# mkwatch_btm.net
KiCad netlist of a schematic drawn in EAGLE
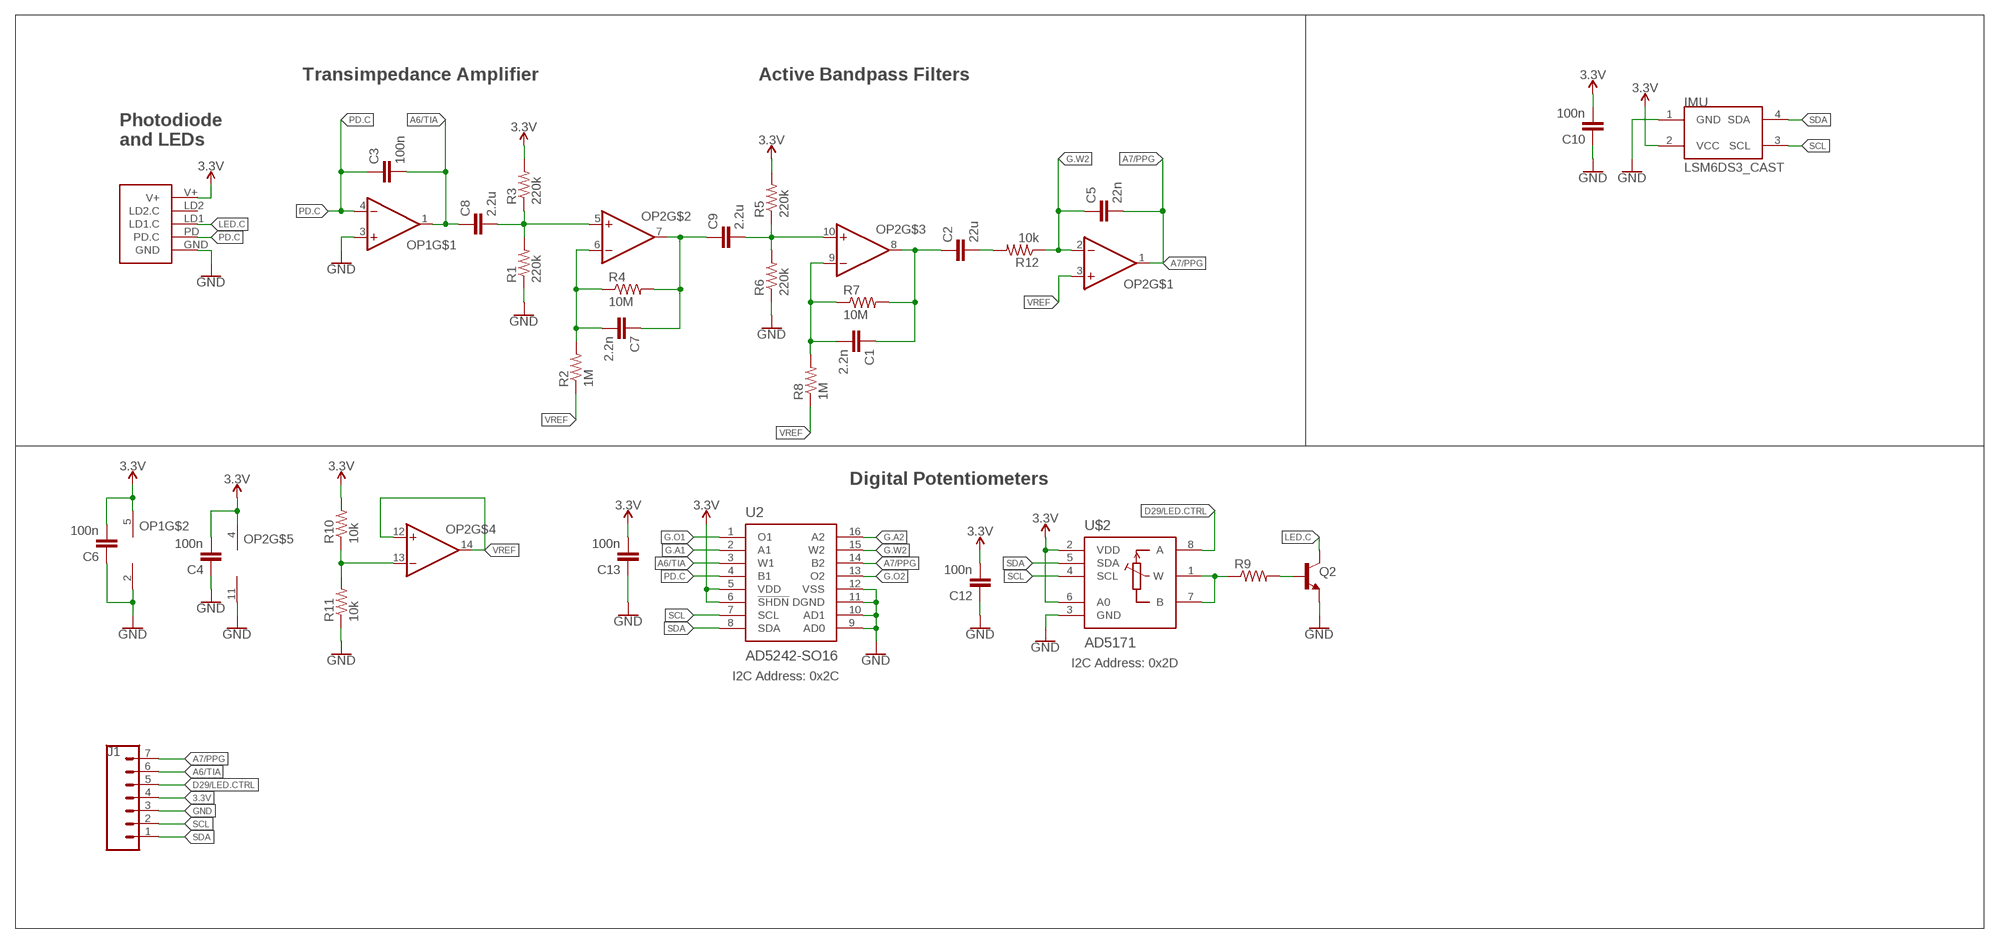
[diagram p0: schematic, sheet 1]

(export (version "E")
  (design (tool "Eeschema 10.0.6"))
  (components
    (comp (ref "C1")
      (value "2.2n")
      (footprint "eagle-import:C0603")
      (libsource (lib "eagle-import") (part "CAPACITOR0603"))
    )
    (comp (ref "C2")
      (value "22u")
      (footprint "eagle-import:C0603")
      (libsource (lib "eagle-import") (part "CAPACITOR0603"))
    )
    (comp (ref "C3")
      (value "100n")
      (footprint "eagle-import:C0603")
      (libsource (lib "eagle-import") (part "CAPACITOR0603"))
    )
    (comp (ref "C4")
      (value "100n")
      (footprint "eagle-import:C0603")
      (libsource (lib "eagle-import") (part "CAPACITOR0603"))
    )
    (comp (ref "C5")
      (value "22n")
      (footprint "eagle-import:C0603")
      (libsource (lib "eagle-import") (part "CAPACITOR0603"))
    )
    (comp (ref "C6")
      (value "100n")
      (footprint "eagle-import:C0603")
      (libsource (lib "eagle-import") (part "CAPACITOR0603"))
    )
    (comp (ref "C7")
      (value "2.2n")
      (footprint "eagle-import:C0603")
      (libsource (lib "eagle-import") (part "CAPACITOR0603"))
    )
    (comp (ref "C8")
      (value "2.2u")
      (footprint "eagle-import:C0603")
      (libsource (lib "eagle-import") (part "CAPACITOR0603"))
    )
    (comp (ref "C9")
      (value "2.2u")
      (footprint "eagle-import:C0603")
      (libsource (lib "eagle-import") (part "CAPACITOR0603"))
    )
    (comp (ref "C10")
      (value "100n")
      (footprint "eagle-import:C0603")
      (libsource (lib "eagle-import") (part "CAPACITOR0603"))
    )
    (comp (ref "C12")
      (value "100n")
      (footprint "eagle-import:C0603")
      (libsource (lib "eagle-import") (part "CAPACITOR0603"))
    )
    (comp (ref "C13")
      (value "100n")
      (footprint "eagle-import:C0603")
      (libsource (lib "eagle-import") (part "CAPACITOR0603"))
    )
    (comp (ref "IMU")
      (value "LSM6DS3_CAST")
      (footprint "eagle-import:LSM6DS3_CAST")
      (libsource (lib "eagle-import") (part "LSM6DS3_CAST"))
    )
    (comp (ref "J1")
      (value "CONN_07-1.27MM")
      (footprint "eagle-import:1X07_1.27MM")
      (libsource (lib "eagle-import") (part "CONN_07-1.27MM"))
    )
    (comp (ref "OP1")
      (value "OP-SINGLEOT")
      (footprint "eagle-import:SOT23-5")
      (libsource (lib "eagle-import") (part "OP-SINGLEOT"))
    )
    (comp (ref "OP2")
      (value "OP-QUAD-SO14")
      (footprint "eagle-import:SO14")
      (libsource (lib "eagle-import") (part "OP-QUAD-SO14"))
    )
    (comp (ref "Q2")
      (value "NPN-GENERIC")
      (footprint "eagle-import:SOT23-3")
      (libsource (lib "eagle-import") (part "NPN-GENERIC"))
    )
    (comp (ref "R1")
      (value "220k")
      (footprint "eagle-import:R0603")
      (libsource (lib "eagle-import") (part "RESISTOR0603"))
    )
    (comp (ref "R2")
      (value "1M")
      (footprint "eagle-import:R0603")
      (libsource (lib "eagle-import") (part "RESISTOR0603"))
    )
    (comp (ref "R3")
      (value "220k")
      (footprint "eagle-import:R0603")
      (libsource (lib "eagle-import") (part "RESISTOR0603"))
    )
    (comp (ref "R4")
      (value "10M")
      (footprint "eagle-import:R0603")
      (libsource (lib "eagle-import") (part "RESISTOR0603"))
    )
    (comp (ref "R5")
      (value "220k")
      (footprint "eagle-import:R0603")
      (libsource (lib "eagle-import") (part "RESISTOR0603"))
    )
    (comp (ref "R6")
      (value "220k")
      (footprint "eagle-import:R0603")
      (libsource (lib "eagle-import") (part "RESISTOR0603"))
    )
    (comp (ref "R7")
      (value "10M")
      (footprint "eagle-import:R0603")
      (libsource (lib "eagle-import") (part "RESISTOR0603"))
    )
    (comp (ref "R8")
      (value "1M")
      (footprint "eagle-import:R0603")
      (libsource (lib "eagle-import") (part "RESISTOR0603"))
    )
    (comp (ref "R9")
      (value "RESISTOR0603")
      (footprint "eagle-import:R0603")
      (libsource (lib "eagle-import") (part "RESISTOR0603"))
    )
    (comp (ref "R10")
      (value "10k")
      (footprint "eagle-import:R0402")
      (libsource (lib "eagle-import") (part "RESISTOR0402"))
    )
    (comp (ref "R11")
      (value "10k")
      (footprint "eagle-import:R0402")
      (libsource (lib "eagle-import") (part "RESISTOR0402"))
    )
    (comp (ref "R12")
      (value "10k")
      (footprint "eagle-import:R0603")
      (libsource (lib "eagle-import") (part "RESISTOR0603"))
    )
    (comp (ref "U$1")
      (value "PPG.MODULE.2")
      (footprint "eagle-import:PPG.MODULE.2")
      (libsource (lib "eagle-import") (part "PPG.MODULE.2"))
    )
    (comp (ref "U$2")
      (value "AD5171")
      (footprint "eagle-import:SOT-23-8")
      (libsource (lib "eagle-import") (part "AD5171"))
    )
    (comp (ref "U2")
      (value "AD5242-SO16")
      (footprint "eagle-import:SO16")
      (libsource (lib "eagle-import") (part "AD5242-SO16"))
    )
  )
  (nets
    (net (code "1") (name "3.3V") (class "Default")
      (node (ref "C10") (pin "2") (pinfunction "2_2") (pintype "passive"))
      (node (ref "C12") (pin "2") (pinfunction "2_2") (pintype "passive"))
      (node (ref "C13") (pin "2") (pinfunction "2_2") (pintype "passive"))
      (node (ref "C4") (pin "2") (pinfunction "2_2") (pintype "passive"))
      (node (ref "C6") (pin "2") (pinfunction "2_2") (pintype "passive"))
      (node (ref "IMU") (pin "2") (pinfunction "VCC_2") (pintype "bidirectional"))
      (node (ref "J1") (pin "4") (pinfunction "4_4") (pintype "passive"))
      (node (ref "OP1") (pin "5") (pinfunction "V+_5") (pintype "power_in"))
      (node (ref "OP2") (pin "4") (pinfunction "V+_4") (pintype "power_in"))
      (node (ref "R10") (pin "2") (pinfunction "2_2") (pintype "passive"))
      (node (ref "R3") (pin "2") (pinfunction "2_2") (pintype "passive"))
      (node (ref "R5") (pin "2") (pinfunction "2_2") (pintype "passive"))
      (node (ref "U$1") (pin "V+") (pinfunction "V+_V+") (pintype "bidirectional"))
      (node (ref "U$2") (pin "2") (pinfunction "VDD_2") (pintype "bidirectional"))
      (node (ref "U$2") (pin "6") (pinfunction "A0_6") (pintype "bidirectional"))
      (node (ref "U2") (pin "5") (pinfunction "VDD_5") (pintype "bidirectional"))
      (node (ref "U2") (pin "6") (pinfunction "~{SHDN}_6") (pintype "bidirectional"))
    )
    (net (code "2") (name "A6{slash}TIA") (class "Default")
      (node (ref "C3") (pin "2") (pinfunction "2_2") (pintype "passive"))
      (node (ref "C8") (pin "1") (pinfunction "1_1") (pintype "passive"))
      (node (ref "J1") (pin "6") (pinfunction "6_6") (pintype "passive"))
      (node (ref "OP1") (pin "1") (pinfunction "OUT_1") (pintype "output"))
      (node (ref "U2") (pin "3") (pinfunction "W1_3") (pintype "bidirectional"))
    )
    (net (code "3") (name "A7{slash}PPG") (class "Default")
      (node (ref "C5") (pin "2") (pinfunction "2_2") (pintype "passive"))
      (node (ref "J1") (pin "7") (pinfunction "7_7") (pintype "passive"))
      (node (ref "OP2") (pin "1") (pinfunction "OUT_1") (pintype "output"))
      (node (ref "U2") (pin "14") (pinfunction "B2_14") (pintype "bidirectional"))
    )
    (net (code "4") (name "D29{slash}LED.CTRL") (class "Default")
      (node (ref "J1") (pin "5") (pinfunction "5_5") (pintype "passive"))
      (node (ref "U$2") (pin "8") (pinfunction "A_8") (pintype "bidirectional"))
    )
    (net (code "5") (name "G.A1") (class "Default")
      (node (ref "U2") (pin "2") (pinfunction "A1_2") (pintype "bidirectional"))
    )
    (net (code "6") (name "G.A2") (class "Default")
      (node (ref "U2") (pin "16") (pinfunction "A2_16") (pintype "bidirectional"))
    )
    (net (code "7") (name "G.O1") (class "Default")
      (node (ref "U2") (pin "1") (pinfunction "O1_1") (pintype "bidirectional"))
    )
    (net (code "8") (name "G.O2") (class "Default")
      (node (ref "U2") (pin "13") (pinfunction "O2_13") (pintype "bidirectional"))
    )
    (net (code "9") (name "G.W2") (class "Default")
      (node (ref "C5") (pin "1") (pinfunction "1_1") (pintype "passive"))
      (node (ref "OP2") (pin "2") (pinfunction "-IN_2") (pintype "input"))
      (node (ref "R12") (pin "1") (pinfunction "1_1") (pintype "passive"))
      (node (ref "U2") (pin "15") (pinfunction "W2_15") (pintype "bidirectional"))
    )
    (net (code "10") (name "GND") (class "Default")
      (node (ref "C10") (pin "1") (pinfunction "1_1") (pintype "passive"))
      (node (ref "C12") (pin "1") (pinfunction "1_1") (pintype "passive"))
      (node (ref "C13") (pin "1") (pinfunction "1_1") (pintype "passive"))
      (node (ref "C4") (pin "1") (pinfunction "1_1") (pintype "passive"))
      (node (ref "C6") (pin "1") (pinfunction "1_1") (pintype "passive"))
      (node (ref "IMU") (pin "1") (pinfunction "GND_1") (pintype "bidirectional"))
      (node (ref "J1") (pin "3") (pinfunction "3_3") (pintype "passive"))
      (node (ref "OP1") (pin "2") (pinfunction "V-_2") (pintype "power_in"))
      (node (ref "OP1") (pin "3") (pinfunction "+IN_3") (pintype "input"))
      (node (ref "OP2") (pin "11") (pinfunction "V-_11") (pintype "power_in"))
      (node (ref "Q2") (pin "2") (pinfunction "E_2") (pintype "passive"))
      (node (ref "R1") (pin "1") (pinfunction "1_1") (pintype "passive"))
      (node (ref "R11") (pin "1") (pinfunction "1_1") (pintype "passive"))
      (node (ref "R6") (pin "1") (pinfunction "1_1") (pintype "passive"))
      (node (ref "U$1") (pin "GND") (pinfunction "GND_GND") (pintype "bidirectional"))
      (node (ref "U$2") (pin "3") (pinfunction "GND_3") (pintype "bidirectional"))
      (node (ref "U2") (pin "10") (pinfunction "AD1_10") (pintype "bidirectional"))
      (node (ref "U2") (pin "11") (pinfunction "DGND_11") (pintype "bidirectional"))
      (node (ref "U2") (pin "12") (pinfunction "VSS_12") (pintype "bidirectional"))
      (node (ref "U2") (pin "9") (pinfunction "AD0_9") (pintype "bidirectional"))
    )
    (net (code "11") (name "LED.C") (class "Default")
      (node (ref "Q2") (pin "3") (pinfunction "C_3") (pintype "passive"))
      (node (ref "U$1") (pin "LD1") (pinfunction "LD1.C_LD1") (pintype "bidirectional"))
    )
    (net (code "12") (name "Net-(C2-Pad2)") (class "Default")
      (node (ref "C2") (pin "2") (pinfunction "2_2") (pintype "passive"))
      (node (ref "R12") (pin "2") (pinfunction "2_2") (pintype "passive"))
    )
    (net (code "13") (name "Net-(OP2B-+IN)") (class "Default")
      (node (ref "C8") (pin "2") (pinfunction "2_2") (pintype "passive"))
      (node (ref "OP2") (pin "5") (pinfunction "+IN_5") (pintype "input"))
      (node (ref "R1") (pin "2") (pinfunction "2_2") (pintype "passive"))
      (node (ref "R3") (pin "1") (pinfunction "1_1") (pintype "passive"))
    )
    (net (code "14") (name "Net-(OP2B--IN)") (class "Default")
      (node (ref "C7") (pin "2") (pinfunction "2_2") (pintype "passive"))
      (node (ref "OP2") (pin "6") (pinfunction "-IN_6") (pintype "input"))
      (node (ref "R2") (pin "2") (pinfunction "2_2") (pintype "passive"))
      (node (ref "R4") (pin "1") (pinfunction "1_1") (pintype "passive"))
    )
    (net (code "15") (name "Net-(OP2B-OUT)") (class "Default")
      (node (ref "C7") (pin "1") (pinfunction "1_1") (pintype "passive"))
      (node (ref "C9") (pin "1") (pinfunction "1_1") (pintype "passive"))
      (node (ref "OP2") (pin "7") (pinfunction "OUT_7") (pintype "output"))
      (node (ref "R4") (pin "2") (pinfunction "2_2") (pintype "passive"))
    )
    (net (code "16") (name "Net-(OP2C-+IN)") (class "Default")
      (node (ref "C9") (pin "2") (pinfunction "2_2") (pintype "passive"))
      (node (ref "OP2") (pin "10") (pinfunction "+IN_10") (pintype "input"))
      (node (ref "R5") (pin "1") (pinfunction "1_1") (pintype "passive"))
      (node (ref "R6") (pin "2") (pinfunction "2_2") (pintype "passive"))
    )
    (net (code "17") (name "Net-(OP2C--IN)") (class "Default")
      (node (ref "C1") (pin "2") (pinfunction "2_2") (pintype "passive"))
      (node (ref "OP2") (pin "9") (pinfunction "-IN_9") (pintype "input"))
      (node (ref "R7") (pin "1") (pinfunction "1_1") (pintype "passive"))
      (node (ref "R8") (pin "2") (pinfunction "2_2") (pintype "passive"))
    )
    (net (code "18") (name "Net-(OP2C-OUT)") (class "Default")
      (node (ref "C1") (pin "1") (pinfunction "1_1") (pintype "passive"))
      (node (ref "C2") (pin "1") (pinfunction "1_1") (pintype "passive"))
      (node (ref "OP2") (pin "8") (pinfunction "OUT_8") (pintype "output"))
      (node (ref "R7") (pin "2") (pinfunction "2_2") (pintype "passive"))
    )
    (net (code "19") (name "Net-(OP2D--IN)") (class "Default")
      (node (ref "OP2") (pin "13") (pinfunction "-IN_13") (pintype "input"))
      (node (ref "R10") (pin "1") (pinfunction "1_1") (pintype "passive"))
      (node (ref "R11") (pin "2") (pinfunction "2_2") (pintype "passive"))
    )
    (net (code "20") (name "Net-(Q2-B)") (class "Default")
      (node (ref "Q2") (pin "1") (pinfunction "B_1") (pintype "passive"))
      (node (ref "R9") (pin "2") (pinfunction "2_2") (pintype "passive"))
    )
    (net (code "21") (name "Net-(U$2-B)") (class "Default")
      (node (ref "R9") (pin "1") (pinfunction "1_1") (pintype "passive"))
      (node (ref "U$2") (pin "1") (pinfunction "W_1") (pintype "bidirectional"))
      (node (ref "U$2") (pin "7") (pinfunction "B_7") (pintype "bidirectional"))
    )
    (net (code "22") (name "PD.C") (class "Default")
      (node (ref "C3") (pin "1") (pinfunction "1_1") (pintype "passive"))
      (node (ref "OP1") (pin "4") (pinfunction "-IN_4") (pintype "input"))
      (node (ref "U$1") (pin "PD") (pinfunction "PD.C_PD") (pintype "bidirectional"))
      (node (ref "U2") (pin "4") (pinfunction "B1_4") (pintype "bidirectional"))
    )
    (net (code "23") (name "SCL") (class "Default")
      (node (ref "IMU") (pin "3") (pinfunction "SCL_3") (pintype "bidirectional"))
      (node (ref "J1") (pin "2") (pinfunction "2_2") (pintype "passive"))
      (node (ref "U$2") (pin "4") (pinfunction "SCL_4") (pintype "bidirectional"))
      (node (ref "U2") (pin "7") (pinfunction "SCL_7") (pintype "bidirectional"))
    )
    (net (code "24") (name "SDA") (class "Default")
      (node (ref "IMU") (pin "4") (pinfunction "SDA_4") (pintype "bidirectional"))
      (node (ref "J1") (pin "1") (pinfunction "1_1") (pintype "passive"))
      (node (ref "U$2") (pin "5") (pinfunction "SDA_5") (pintype "bidirectional"))
      (node (ref "U2") (pin "8") (pinfunction "SDA_8") (pintype "bidirectional"))
    )
    (net (code "25") (name "VREF") (class "Default")
      (node (ref "OP2") (pin "12") (pinfunction "+IN_12") (pintype "input"))
      (node (ref "OP2") (pin "14") (pinfunction "OUT_14") (pintype "output"))
      (node (ref "OP2") (pin "3") (pinfunction "+IN_3") (pintype "input"))
      (node (ref "R2") (pin "1") (pinfunction "1_1") (pintype "passive"))
      (node (ref "R8") (pin "1") (pinfunction "1_1") (pintype "passive"))
    )
    (net (code "26") (name "unconnected-(U$1-LD2.C-PadLD2)") (class "Default")
      (node (ref "U$1") (pin "LD2") (pinfunction "LD2.C_LD2") (pintype "bidirectional"))
    )
  )
)
